# TM8_flash.net
KiCad netlist of a schematic drawn in EAGLE
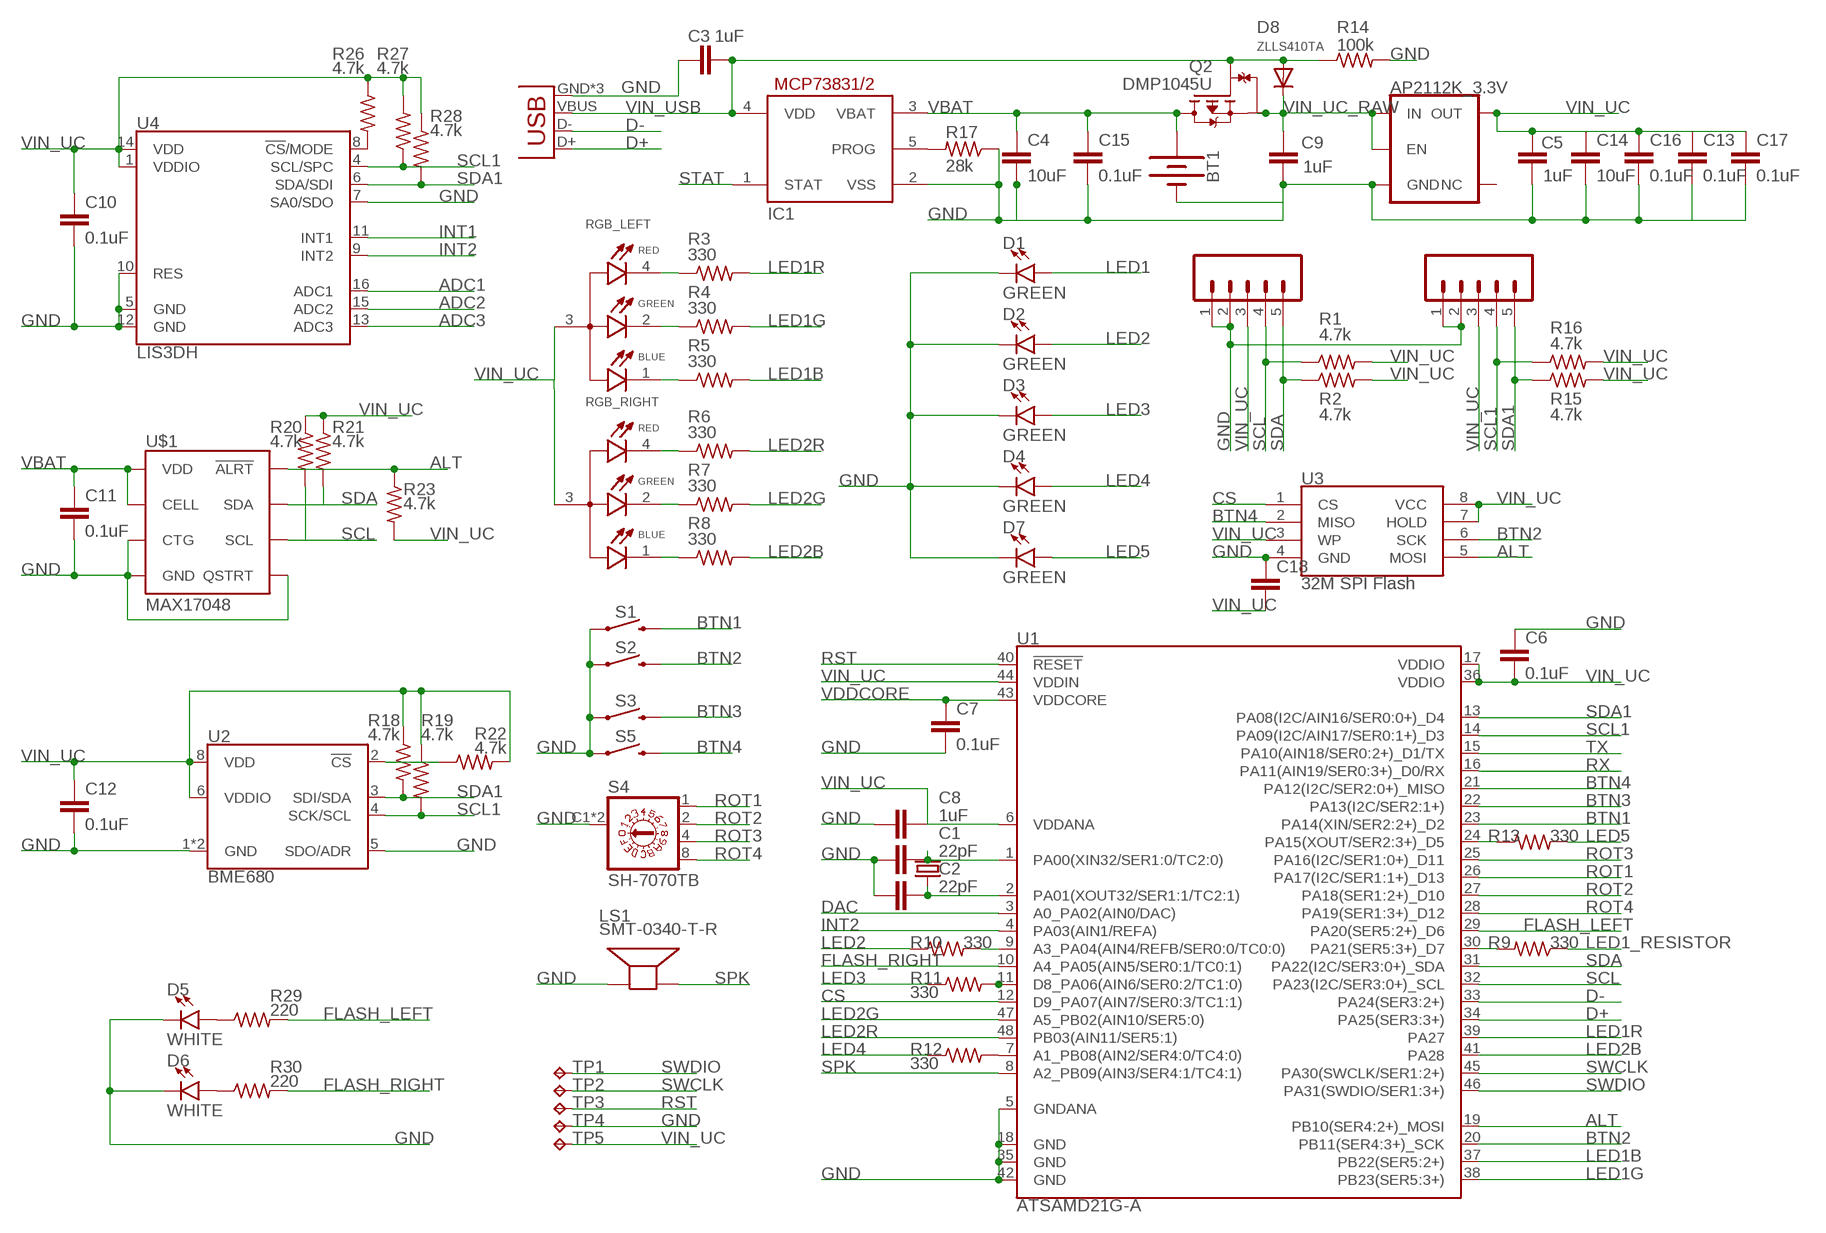
[diagram p0: schematic, sheet 1]

(export (version "E")
  (design (tool "Eeschema 10.0.6"))
  (components
    (comp (ref "AP2112K_3.3V")
      (value "3.3V")
      (footprint "eagle-import:SOT23-5")
      (libsource (lib "eagle-import") (part "V_REG_AP2112K-3.3V"))
    )
    (comp (ref "BT1")
      (value "BATTERY-20MM_SMD_4LEGS_OVERPASTE_INNER")
      (footprint "eagle-import:BATTCON_20MM_4LEGS_OVERPASTE_INNER")
      (libsource (lib "eagle-import") (part "BATTERY-20MM_SMD_4LEGS_OVERPASTE_INNER"))
    )
    (comp (ref "C1")
      (value "22pF")
      (footprint "eagle-import:C0402")
      (libsource (lib "eagle-import") (part "C-EUC0402"))
    )
    (comp (ref "C2")
      (value "22pF")
      (footprint "eagle-import:C0402")
      (libsource (lib "eagle-import") (part "C-EUC0402"))
    )
    (comp (ref "C3")
      (value "1uF")
      (footprint "eagle-import:C0402")
      (libsource (lib "eagle-import") (part "C-EUC0402"))
    )
    (comp (ref "C4")
      (value "10uF")
      (footprint "eagle-import:C0402")
      (libsource (lib "eagle-import") (part "C-EUC0402"))
    )
    (comp (ref "C5")
      (value "1uF")
      (footprint "eagle-import:C0402")
      (libsource (lib "eagle-import") (part "C-EUC0402"))
    )
    (comp (ref "C6")
      (value "0.1uF")
      (footprint "eagle-import:C0402")
      (libsource (lib "eagle-import") (part "C-EUC0402"))
    )
    (comp (ref "C7")
      (value "0.1uF")
      (footprint "eagle-import:C0402")
      (libsource (lib "eagle-import") (part "C-EUC0402"))
    )
    (comp (ref "C8")
      (value "1uF")
      (footprint "eagle-import:C0402")
      (libsource (lib "eagle-import") (part "C-EUC0402"))
    )
    (comp (ref "C9")
      (value "1uF")
      (footprint "eagle-import:C0402")
      (libsource (lib "eagle-import") (part "C-EUC0402"))
    )
    (comp (ref "C10")
      (value "0.1uF")
      (footprint "eagle-import:C0402")
      (libsource (lib "eagle-import") (part "C-EUC0402"))
    )
    (comp (ref "C11")
      (value "0.1uF")
      (footprint "eagle-import:C0402")
      (libsource (lib "eagle-import") (part "C-EUC0402"))
    )
    (comp (ref "C12")
      (value "0.1uF")
      (footprint "eagle-import:C0402")
      (libsource (lib "eagle-import") (part "C-EUC0402"))
    )
    (comp (ref "C13")
      (value "0.1uF")
      (footprint "eagle-import:C0402")
      (libsource (lib "eagle-import") (part "C-EUC0402"))
    )
    (comp (ref "C14")
      (value "10uF")
      (footprint "eagle-import:C0402")
      (libsource (lib "eagle-import") (part "C-EUC0402"))
    )
    (comp (ref "C15")
      (value "0.1uF")
      (footprint "eagle-import:C0402")
      (libsource (lib "eagle-import") (part "C-EUC0402"))
    )
    (comp (ref "C16")
      (value "0.1uF")
      (footprint "eagle-import:C0402")
      (libsource (lib "eagle-import") (part "C-EUC0402"))
    )
    (comp (ref "C17")
      (value "0.1uF")
      (footprint "eagle-import:C0402")
      (libsource (lib "eagle-import") (part "C-EUC0402"))
    )
    (comp (ref "C18")
      (value "C-EUC0402")
      (footprint "eagle-import:C0402")
      (libsource (lib "eagle-import") (part "C-EUC0402"))
    )
    (comp (ref "D1")
      (value "GREEN")
      (footprint "eagle-import:LED-1206")
      (libsource (lib "eagle-import") (part "LED-GREEN1206"))
    )
    (comp (ref "D2")
      (value "GREEN")
      (footprint "eagle-import:LED-1206")
      (libsource (lib "eagle-import") (part "LED-GREEN1206"))
    )
    (comp (ref "D3")
      (value "GREEN")
      (footprint "eagle-import:LED-1206")
      (libsource (lib "eagle-import") (part "LED-GREEN1206"))
    )
    (comp (ref "D4")
      (value "GREEN")
      (footprint "eagle-import:LED-1206")
      (libsource (lib "eagle-import") (part "LED-GREEN1206"))
    )
    (comp (ref "D5")
      (value "WHITE")
      (footprint "eagle-import:LED-1206")
      (libsource (lib "eagle-import") (part "LED-WHITE1206"))
    )
    (comp (ref "D6")
      (value "WHITE")
      (footprint "eagle-import:LED-1206")
      (libsource (lib "eagle-import") (part "LED-WHITE1206"))
    )
    (comp (ref "D7")
      (value "GREEN")
      (footprint "eagle-import:LED-1206")
      (libsource (lib "eagle-import") (part "LED-GREEN1206"))
    )
    (comp (ref "D8")
      (value "ZLLS410TA")
      (footprint "eagle-import:SOD-323F")
      (libsource (lib "eagle-import") (part "DIODESOD-323F"))
    )
    (comp (ref "IC1")
      (value "MCP73831/OT")
      (footprint "eagle-import:SOT23-5L")
      (libsource (lib "eagle-import") (part "MCP73831/OT"))
    )
    (comp (ref "JP2")
      (value "USB-MICROB")
      (footprint "eagle-import:USB-MICROB")
      (libsource (lib "eagle-import") (part "USB-MICROB"))
    )
    (comp (ref "LCD1")
      (value "CONN_05VERT_FEMALE_HEADER")
      (footprint "eagle-import:1X05_SMD_VERTICAL_COMBO")
      (libsource (lib "eagle-import") (part "CONN_05VERT_FEMALE_HEADER"))
    )
    (comp (ref "LCD2")
      (value "CONN_05VERT_FEMALE_HEADER")
      (footprint "eagle-import:1X05_SMD_VERTICAL_COMBO")
      (libsource (lib "eagle-import") (part "CONN_05VERT_FEMALE_HEADER"))
    )
    (comp (ref "LS1")
      (value "SMT-0340-T-R")
      (footprint "eagle-import:XDCR_SMT-0340-T-R")
      (fields (field (name "MANUFACTURER") "Pui Audio"))
      (libsource (lib "eagle-import") (part "SMT-0340-T-R"))
    )
    (comp (ref "Q2")
      (value "DMP1045U")
      (footprint "eagle-import:SOT91P240X110-3N")
      (fields (field (name "MF") "Diodes Inc."))
      (libsource (lib "eagle-import") (part "DMP1045U"))
    )
    (comp (ref "R1")
      (value "4.7k")
      (footprint "eagle-import:R0402")
      (libsource (lib "eagle-import") (part "rcl_334_R-US_R0402"))
    )
    (comp (ref "R2")
      (value "4.7k")
      (footprint "eagle-import:R0402")
      (libsource (lib "eagle-import") (part "rcl_334_R-US_R0402"))
    )
    (comp (ref "R3")
      (value "330")
      (footprint "eagle-import:R0402")
      (libsource (lib "eagle-import") (part "rcl_334_R-US_R0402"))
    )
    (comp (ref "R4")
      (value "330")
      (footprint "eagle-import:R0402")
      (libsource (lib "eagle-import") (part "rcl_334_R-US_R0402"))
    )
    (comp (ref "R5")
      (value "330")
      (footprint "eagle-import:R0402")
      (libsource (lib "eagle-import") (part "rcl_334_R-US_R0402"))
    )
    (comp (ref "R6")
      (value "330")
      (footprint "eagle-import:R0402")
      (libsource (lib "eagle-import") (part "rcl_334_R-US_R0402"))
    )
    (comp (ref "R7")
      (value "330")
      (footprint "eagle-import:R0402")
      (libsource (lib "eagle-import") (part "rcl_334_R-US_R0402"))
    )
    (comp (ref "R8")
      (value "330")
      (footprint "eagle-import:R0402")
      (libsource (lib "eagle-import") (part "rcl_334_R-US_R0402"))
    )
    (comp (ref "R9")
      (value "330")
      (footprint "eagle-import:R0402")
      (libsource (lib "eagle-import") (part "rcl_334_R-US_R0402"))
    )
    (comp (ref "R10")
      (value "330")
      (footprint "eagle-import:R0402")
      (libsource (lib "eagle-import") (part "rcl_334_R-US_R0402"))
    )
    (comp (ref "R11")
      (value "330")
      (footprint "eagle-import:R0402")
      (libsource (lib "eagle-import") (part "rcl_334_R-US_R0402"))
    )
    (comp (ref "R12")
      (value "330")
      (footprint "eagle-import:R0402")
      (libsource (lib "eagle-import") (part "rcl_334_R-US_R0402"))
    )
    (comp (ref "R13")
      (value "330")
      (footprint "eagle-import:R0402")
      (libsource (lib "eagle-import") (part "rcl_334_R-US_R0402"))
    )
    (comp (ref "R14")
      (value "100k")
      (footprint "eagle-import:R0402")
      (libsource (lib "eagle-import") (part "R-US_R0402"))
    )
    (comp (ref "R15")
      (value "4.7k")
      (footprint "eagle-import:R0402")
      (libsource (lib "eagle-import") (part "rcl_334_R-US_R0402"))
    )
    (comp (ref "R16")
      (value "4.7k")
      (footprint "eagle-import:R0402")
      (libsource (lib "eagle-import") (part "rcl_334_R-US_R0402"))
    )
    (comp (ref "R17")
      (value "28k")
      (footprint "eagle-import:R0402")
      (libsource (lib "eagle-import") (part "adafruit_25768682_R-US_R0402"))
    )
    (comp (ref "R18")
      (value "4.7k")
      (footprint "eagle-import:R0402")
      (libsource (lib "eagle-import") (part "rcl_334_R-US_R0402"))
    )
    (comp (ref "R19")
      (value "4.7k")
      (footprint "eagle-import:R0402")
      (libsource (lib "eagle-import") (part "rcl_334_R-US_R0402"))
    )
    (comp (ref "R20")
      (value "4.7k")
      (footprint "eagle-import:R0402")
      (libsource (lib "eagle-import") (part "rcl_334_R-US_R0402"))
    )
    (comp (ref "R21")
      (value "4.7k")
      (footprint "eagle-import:R0402")
      (libsource (lib "eagle-import") (part "rcl_334_R-US_R0402"))
    )
    (comp (ref "R22")
      (value "4.7k")
      (footprint "eagle-import:R0402")
      (libsource (lib "eagle-import") (part "rcl_334_R-US_R0402"))
    )
    (comp (ref "R23")
      (value "4.7k")
      (footprint "eagle-import:R0402")
      (libsource (lib "eagle-import") (part "rcl_334_R-US_R0402"))
    )
    (comp (ref "R26")
      (value "4.7k")
      (footprint "eagle-import:R0402")
      (libsource (lib "eagle-import") (part "rcl_334_R-US_R0402"))
    )
    (comp (ref "R27")
      (value "4.7k")
      (footprint "eagle-import:R0402")
      (libsource (lib "eagle-import") (part "rcl_334_R-US_R0402"))
    )
    (comp (ref "R28")
      (value "4.7k")
      (footprint "eagle-import:R0402")
      (libsource (lib "eagle-import") (part "rcl_334_R-US_R0402"))
    )
    (comp (ref "R29")
      (value "220")
      (footprint "eagle-import:R0402")
      (libsource (lib "eagle-import") (part "rcl_334_R-US_R0402"))
    )
    (comp (ref "R30")
      (value "220")
      (footprint "eagle-import:R0402")
      (libsource (lib "eagle-import") (part "rcl_334_R-US_R0402"))
    )
    (comp (ref "RGB_LEFT")
      (value "EAST1616RGBA3")
      (footprint "eagle-import:LED_EAST1616RGBA3")
      (fields (field (name "MF") "Everlight Electronics"))
      (libsource (lib "eagle-import") (part "EAST1616RGBA3"))
    )
    (comp (ref "RGB_RIGHT")
      (value "EAST1616RGBA3")
      (footprint "eagle-import:LED_EAST1616RGBA3")
      (fields (field (name "MF") "Everlight Electronics"))
      (libsource (lib "eagle-import") (part "EAST1616RGBA3"))
    )
    (comp (ref "S1")
      (value "MOMENTARY-SWITCH-SPST-SMD-6.0X3.5MM")
      (footprint "eagle-import:TACTILE_SWITCH_SMD_6.0X3.5MM")
      (libsource (lib "eagle-import") (part "MOMENTARY-SWITCH-SPST-SMD-6.0X3.5MM"))
    )
    (comp (ref "S2")
      (value "MOMENTARY-SWITCH-SPST-SMD-6.0X3.5MM")
      (footprint "eagle-import:TACTILE_SWITCH_SMD_6.0X3.5MM")
      (libsource (lib "eagle-import") (part "MOMENTARY-SWITCH-SPST-SMD-6.0X3.5MM"))
    )
    (comp (ref "S3")
      (value "MOMENTARY-SWITCH-SPST-SMD-6.0X3.5MM")
      (footprint "eagle-import:TACTILE_SWITCH_SMD_6.0X3.5MM")
      (libsource (lib "eagle-import") (part "MOMENTARY-SWITCH-SPST-SMD-6.0X3.5MM"))
    )
    (comp (ref "S4")
      (value "SH-7070TB")
      (footprint "eagle-import:SH-7070B")
      (fields (field (name "MF") "Nidec Copal"))
      (libsource (lib "eagle-import") (part "SH-7070TB"))
    )
    (comp (ref "S5")
      (value "MOMENTARY-SWITCH-SPST-SMD-6.0X3.5MM")
      (footprint "eagle-import:TACTILE_SWITCH_SMD_6.0X3.5MM")
      (libsource (lib "eagle-import") (part "MOMENTARY-SWITCH-SPST-SMD-6.0X3.5MM"))
    )
    (comp (ref "TP1")
      (value "TPTP14R")
      (footprint "eagle-import:TP14R")
      (libsource (lib "eagle-import") (part "TPTP14R"))
    )
    (comp (ref "TP2")
      (value "TPTP14R")
      (footprint "eagle-import:TP14R")
      (libsource (lib "eagle-import") (part "TPTP14R"))
    )
    (comp (ref "TP3")
      (value "TPTP11R")
      (footprint "eagle-import:TP11R")
      (libsource (lib "eagle-import") (part "TPTP11R"))
    )
    (comp (ref "TP4")
      (value "TPTP14R")
      (footprint "eagle-import:TP14R")
      (libsource (lib "eagle-import") (part "TPTP14R"))
    )
    (comp (ref "TP5")
      (value "TPTP14R")
      (footprint "eagle-import:TP14R")
      (libsource (lib "eagle-import") (part "TPTP14R"))
    )
    (comp (ref "U$1")
      (value "MAX17048")
      (footprint "eagle-import:DFN-8")
      (libsource (lib "eagle-import") (part "MAX17048DFN8"))
    )
    (comp (ref "U1")
      (value "ATSAMD21G-A")
      (footprint "eagle-import:TQFP-48")
      (libsource (lib "eagle-import") (part "ATSAMD21G-A"))
    )
    (comp (ref "U2")
      (value "BME680")
      (footprint "eagle-import:LGA3.0X3.0")
      (libsource (lib "eagle-import") (part "BME680-LGA"))
    )
    (comp (ref "U3")
      (value "32M SPI Flash")
      (footprint "eagle-import:SO08")
      (libsource (lib "eagle-import") (part "SPI_FLASH-X25XXSMD"))
    )
    (comp (ref "U4")
      (value "LIS3DH")
      (footprint "eagle-import:LGA-16-3X3")
      (libsource (lib "eagle-import") (part "LIS3DH"))
    )
    (comp (ref "Y1")
      (value "32.768kHz")
      (footprint "eagle-import:CRYSTAL-SMD-3.2X1.5MM")
      (libsource (lib "eagle-import") (part "CRYSTAL-32.768KHZSMD-3.2X1.5"))
    )
  )
  (nets
    (net (code "1") (name "/ADC1") (class "Default")
      (node (ref "U4") (pin "16") (pinfunction "ADC1_16") (pintype "bidirectional"))
    )
    (net (code "2") (name "/ADC2") (class "Default")
      (node (ref "U4") (pin "15") (pinfunction "ADC2_15") (pintype "bidirectional"))
    )
    (net (code "3") (name "/ADC3") (class "Default")
      (node (ref "U4") (pin "13") (pinfunction "ADC3_13") (pintype "bidirectional"))
    )
    (net (code "4") (name "/ALT") (class "Default")
      (node (ref "R23") (pin "1") (pinfunction "1_1") (pintype "passive"))
      (node (ref "U$1") (pin "P$5") (pinfunction "~{ALRT}_P$5") (pintype "bidirectional"))
      (node (ref "U1") (pin "19") (pinfunction "PB10(SER4:2+)_MOSI_19") (pintype "bidirectional"))
      (node (ref "U3") (pin "5") (pinfunction "MOSI_5") (pintype "bidirectional"))
    )
    (net (code "5") (name "/BTN1") (class "Default")
      (node (ref "S1") (pin "2") (pinfunction "2_2") (pintype "passive"))
      (node (ref "U1") (pin "23") (pinfunction "PA14(XIN/SER2:2+)_D2_23") (pintype "bidirectional"))
    )
    (net (code "6") (name "/BTN2") (class "Default")
      (node (ref "S2") (pin "2") (pinfunction "2_2") (pintype "passive"))
      (node (ref "U1") (pin "20") (pinfunction "PB11(SER4:3+)_SCK_20") (pintype "bidirectional"))
      (node (ref "U3") (pin "6") (pinfunction "SCK_6") (pintype "bidirectional"))
    )
    (net (code "7") (name "/BTN3") (class "Default")
      (node (ref "S3") (pin "2") (pinfunction "2_2") (pintype "passive"))
      (node (ref "U1") (pin "22") (pinfunction "PA13(I2C/SER2:1+)_22") (pintype "bidirectional"))
    )
    (net (code "8") (name "/BTN4") (class "Default")
      (node (ref "S5") (pin "2") (pinfunction "2_2") (pintype "passive"))
      (node (ref "U1") (pin "21") (pinfunction "PA12(I2C/SER2:0+)_MISO_21") (pintype "bidirectional"))
      (node (ref "U3") (pin "2") (pinfunction "MISO_2") (pintype "bidirectional"))
    )
    (net (code "9") (name "/CS") (class "Default")
      (node (ref "U1") (pin "12") (pinfunction "D9_PA07(AIN7/SER0:3/TC1:1)_12") (pintype "bidirectional"))
      (node (ref "U3") (pin "1") (pinfunction "CS_1") (pintype "bidirectional"))
    )
    (net (code "10") (name "/D+") (class "Default")
      (node (ref "JP2") (pin "D+") (pinfunction "D+_D+") (pintype "bidirectional"))
      (node (ref "U1") (pin "34") (pinfunction "PA25(SER3:3+)_34") (pintype "bidirectional"))
    )
    (net (code "11") (name "/D-") (class "Default")
      (node (ref "JP2") (pin "D-") (pinfunction "D-_D-") (pintype "bidirectional"))
      (node (ref "U1") (pin "33") (pinfunction "PA24(SER3:2+)_33") (pintype "bidirectional"))
    )
    (net (code "12") (name "/DAC") (class "Default")
      (node (ref "U1") (pin "3") (pinfunction "A0_PA02(AIN0/DAC)_3") (pintype "bidirectional"))
    )
    (net (code "13") (name "/FLASH_LEFT") (class "Default")
      (node (ref "R29") (pin "2") (pinfunction "2_2") (pintype "passive"))
      (node (ref "U1") (pin "29") (pinfunction "PA20(SER5:2+)_D6_29") (pintype "bidirectional"))
    )
    (net (code "14") (name "/FLASH_RIGHT") (class "Default")
      (node (ref "R30") (pin "2") (pinfunction "2_2") (pintype "passive"))
      (node (ref "U1") (pin "10") (pinfunction "A4_PA05(AIN5/SER0:1/TC0:1)_10") (pintype "bidirectional"))
    )
    (net (code "15") (name "/GND") (class "Default")
      (node (ref "AP2112K_3.3V") (pin "2") (pinfunction "GND_2") (pintype "input"))
      (node (ref "BT1") (pin "2") (pinfunction "-_2") (pintype "power_in"))
      (node (ref "C1") (pin "1") (pinfunction "1_1") (pintype "passive"))
      (node (ref "C10") (pin "2") (pinfunction "2_2") (pintype "passive"))
      (node (ref "C11") (pin "2") (pinfunction "2_2") (pintype "passive"))
      (node (ref "C12") (pin "2") (pinfunction "2_2") (pintype "passive"))
      (node (ref "C13") (pin "2") (pinfunction "2_2") (pintype "passive"))
      (node (ref "C14") (pin "2") (pinfunction "2_2") (pintype "passive"))
      (node (ref "C15") (pin "2") (pinfunction "2_2") (pintype "passive"))
      (node (ref "C16") (pin "2") (pinfunction "2_2") (pintype "passive"))
      (node (ref "C17") (pin "2") (pinfunction "2_2") (pintype "passive"))
      (node (ref "C18") (pin "1") (pinfunction "1_1") (pintype "passive"))
      (node (ref "C2") (pin "1") (pinfunction "1_1") (pintype "passive"))
      (node (ref "C3") (pin "1") (pinfunction "1_1") (pintype "passive"))
      (node (ref "C4") (pin "2") (pinfunction "2_2") (pintype "passive"))
      (node (ref "C5") (pin "2") (pinfunction "2_2") (pintype "passive"))
      (node (ref "C6") (pin "1") (pinfunction "1_1") (pintype "passive"))
      (node (ref "C7") (pin "2") (pinfunction "2_2") (pintype "passive"))
      (node (ref "C8") (pin "1") (pinfunction "1_1") (pintype "passive"))
      (node (ref "C9") (pin "2") (pinfunction "2_2") (pintype "passive"))
      (node (ref "D1") (pin "C") (pinfunction "C_C") (pintype "passive"))
      (node (ref "D2") (pin "C") (pinfunction "C_C") (pintype "passive"))
      (node (ref "D3") (pin "C") (pinfunction "C_C") (pintype "passive"))
      (node (ref "D4") (pin "C") (pinfunction "C_C") (pintype "passive"))
      (node (ref "D5") (pin "C") (pinfunction "C_C") (pintype "passive"))
      (node (ref "D6") (pin "C") (pinfunction "C_C") (pintype "passive"))
      (node (ref "D7") (pin "C") (pinfunction "C_C") (pintype "passive"))
      (node (ref "IC1") (pin "2") (pinfunction "VSS_2") (pintype "power_in"))
      (node (ref "JP2") (pin "GND") (pinfunction "GND_GND") (pintype "bidirectional"))
      (node (ref "JP2") (pin "MT1") (pinfunction "GND_MT1") (pintype "bidirectional"))
      (node (ref "JP2") (pin "MT2") (pinfunction "GND_MT2") (pintype "bidirectional"))
      (node (ref "LCD1") (pin "1") (pinfunction "1_1") (pintype "passive"))
      (node (ref "LCD1") (pin "2") (pinfunction "2_2") (pintype "passive"))
      (node (ref "LCD2") (pin "1") (pinfunction "1_1") (pintype "passive"))
      (node (ref "LCD2") (pin "2") (pinfunction "2_2") (pintype "passive"))
      (node (ref "LS1") (pin "P") (pinfunction "P_P") (pintype "passive"))
      (node (ref "R14") (pin "2") (pinfunction "2_2") (pintype "passive"))
      (node (ref "R17") (pin "1") (pinfunction "1_1") (pintype "passive"))
      (node (ref "S1") (pin "1") (pinfunction "1_1") (pintype "passive"))
      (node (ref "S2") (pin "1") (pinfunction "1_1") (pintype "passive"))
      (node (ref "S3") (pin "1") (pinfunction "1_1") (pintype "passive"))
      (node (ref "S4") (pin "C1") (pinfunction "C_C1") (pintype "passive"))
      (node (ref "S4") (pin "C2") (pinfunction "C_C2") (pintype "passive"))
      (node (ref "S5") (pin "1") (pinfunction "1_1") (pintype "passive"))
      (node (ref "TP4") (pin "TP") (pinfunction "TP_TP") (pintype "input"))
      (node (ref "U$1") (pin "P$1") (pinfunction "CTG_P$1") (pintype "input"))
      (node (ref "U$1") (pin "P$4") (pinfunction "GND_P$4") (pintype "bidirectional"))
      (node (ref "U$1") (pin "P$6") (pinfunction "QSTRT_P$6") (pintype "bidirectional"))
      (node (ref "U$1") (pin "P$9") (pinfunction "GND_P$9") (pintype "bidirectional"))
      (node (ref "U1") (pin "18") (pinfunction "GND_18") (pintype "bidirectional"))
      (node (ref "U1") (pin "35") (pinfunction "GND_35") (pintype "bidirectional"))
      (node (ref "U1") (pin "42") (pinfunction "GND_42") (pintype "bidirectional"))
      (node (ref "U1") (pin "5") (pinfunction "GNDANA_5") (pintype "bidirectional"))
      (node (ref "U2") (pin "1") (pinfunction "GND_1") (pintype "bidirectional"))
      (node (ref "U2") (pin "5") (pinfunction "SDO/ADR_5") (pintype "bidirectional"))
      (node (ref "U2") (pin "7") (pinfunction "GND_7") (pintype "bidirectional"))
      (node (ref "U3") (pin "4") (pinfunction "GND_4") (pintype "power_in"))
      (node (ref "U4") (pin "10") (pinfunction "RES_10") (pintype "bidirectional"))
      (node (ref "U4") (pin "12") (pinfunction "GND_12") (pintype "bidirectional"))
      (node (ref "U4") (pin "5") (pinfunction "GND_5") (pintype "bidirectional"))
      (node (ref "U4") (pin "7") (pinfunction "SA0/SDO_7") (pintype "bidirectional"))
    )
    (net (code "16") (name "/INT1") (class "Default")
      (node (ref "U4") (pin "11") (pinfunction "INT1_11") (pintype "bidirectional"))
    )
    (net (code "17") (name "/INT2") (class "Default")
      (node (ref "U1") (pin "4") (pinfunction "PA03(AIN1/REFA)_4") (pintype "bidirectional"))
      (node (ref "U4") (pin "9") (pinfunction "INT2_9") (pintype "bidirectional"))
    )
    (net (code "18") (name "/LED1") (class "Default")
      (node (ref "D1") (pin "A") (pinfunction "A_A") (pintype "passive"))
    )
    (net (code "19") (name "/LED1B") (class "Default")
      (node (ref "R5") (pin "2") (pinfunction "2_2") (pintype "passive"))
      (node (ref "U1") (pin "37") (pinfunction "PB22(SER5:2+)_37") (pintype "bidirectional"))
    )
    (net (code "20") (name "/LED1G") (class "Default")
      (node (ref "R4") (pin "2") (pinfunction "2_2") (pintype "passive"))
      (node (ref "U1") (pin "38") (pinfunction "PB23(SER5:3+)_38") (pintype "bidirectional"))
    )
    (net (code "21") (name "/LED1R") (class "Default")
      (node (ref "R3") (pin "2") (pinfunction "2_2") (pintype "passive"))
      (node (ref "U1") (pin "39") (pinfunction "PA27_39") (pintype "bidirectional"))
    )
    (net (code "22") (name "/LED1_RESISTOR") (class "Default")
      (node (ref "R9") (pin "1") (pinfunction "1_1") (pintype "passive"))
    )
    (net (code "23") (name "/LED2") (class "Default")
      (node (ref "D2") (pin "A") (pinfunction "A_A") (pintype "passive"))
      (node (ref "R10") (pin "1") (pinfunction "1_1") (pintype "passive"))
    )
    (net (code "24") (name "/LED2B") (class "Default")
      (node (ref "R8") (pin "2") (pinfunction "2_2") (pintype "passive"))
      (node (ref "U1") (pin "41") (pinfunction "PA28_41") (pintype "bidirectional"))
    )
    (net (code "25") (name "/LED2G") (class "Default")
      (node (ref "R7") (pin "2") (pinfunction "2_2") (pintype "passive"))
      (node (ref "U1") (pin "47") (pinfunction "A5_PB02(AIN10/SER5:0)_47") (pintype "bidirectional"))
    )
    (net (code "26") (name "/LED2R") (class "Default")
      (node (ref "R6") (pin "2") (pinfunction "2_2") (pintype "passive"))
      (node (ref "U1") (pin "48") (pinfunction "PB03(AIN11/SER5:1)_48") (pintype "bidirectional"))
    )
    (net (code "27") (name "/LED3") (class "Default")
      (node (ref "D3") (pin "A") (pinfunction "A_A") (pintype "passive"))
      (node (ref "R11") (pin "1") (pinfunction "1_1") (pintype "passive"))
    )
    (net (code "28") (name "/LED4") (class "Default")
      (node (ref "D4") (pin "A") (pinfunction "A_A") (pintype "passive"))
      (node (ref "R12") (pin "1") (pinfunction "1_1") (pintype "passive"))
    )
    (net (code "29") (name "/LED5") (class "Default")
      (node (ref "D7") (pin "A") (pinfunction "A_A") (pintype "passive"))
      (node (ref "R13") (pin "2") (pinfunction "2_2") (pintype "passive"))
    )
    (net (code "30") (name "/ROT1") (class "Default")
      (node (ref "S4") (pin "1") (pinfunction "1_1") (pintype "passive"))
      (node (ref "U1") (pin "26") (pinfunction "PA17(I2C/SER1:1+)_D13_26") (pintype "bidirectional"))
    )
    (net (code "31") (name "/ROT2") (class "Default")
      (node (ref "S4") (pin "2") (pinfunction "2_2") (pintype "passive"))
      (node (ref "U1") (pin "27") (pinfunction "PA18(SER1:2+)_D10_27") (pintype "bidirectional"))
    )
    (net (code "32") (name "/ROT3") (class "Default")
      (node (ref "S4") (pin "4") (pinfunction "4_4") (pintype "passive"))
      (node (ref "U1") (pin "25") (pinfunction "PA16(I2C/SER1:0+)_D11_25") (pintype "bidirectional"))
    )
    (net (code "33") (name "/ROT4") (class "Default")
      (node (ref "S4") (pin "8") (pinfunction "8_8") (pintype "passive"))
      (node (ref "U1") (pin "28") (pinfunction "PA19(SER1:3+)_D12_28") (pintype "bidirectional"))
    )
    (net (code "34") (name "/RST") (class "Default")
      (node (ref "TP3") (pin "TP") (pinfunction "TP_TP") (pintype "input"))
      (node (ref "U1") (pin "40") (pinfunction "~{RESET}_40") (pintype "bidirectional"))
    )
    (net (code "35") (name "/RX") (class "Default")
      (node (ref "U1") (pin "16") (pinfunction "PA11(AIN19/SER0:3+)_D0/RX_16") (pintype "bidirectional"))
    )
    (net (code "36") (name "/SCL") (class "Default")
      (node (ref "LCD1") (pin "4") (pinfunction "4_4") (pintype "passive"))
      (node (ref "R1") (pin "1") (pinfunction "1_1") (pintype "passive"))
      (node (ref "R20") (pin "2") (pinfunction "2_2") (pintype "passive"))
      (node (ref "U$1") (pin "P$7") (pinfunction "SCL_P$7") (pintype "output"))
      (node (ref "U1") (pin "32") (pinfunction "PA23(I2C/SER3:0+)_SCL_32") (pintype "bidirectional"))
    )
    (net (code "37") (name "/SCL1") (class "Default")
      (node (ref "LCD2") (pin "4") (pinfunction "4_4") (pintype "passive"))
      (node (ref "R16") (pin "1") (pinfunction "1_1") (pintype "passive"))
      (node (ref "R19") (pin "2") (pinfunction "2_2") (pintype "passive"))
      (node (ref "R27") (pin "1") (pinfunction "1_1") (pintype "passive"))
      (node (ref "U1") (pin "14") (pinfunction "PA09(I2C/AIN17/SER0:1+)_D3_14") (pintype "bidirectional"))
      (node (ref "U2") (pin "4") (pinfunction "SCK/SCL_4") (pintype "bidirectional"))
      (node (ref "U4") (pin "4") (pinfunction "SCL/SPC_4") (pintype "bidirectional"))
    )
    (net (code "38") (name "/SDA") (class "Default")
      (node (ref "LCD1") (pin "5") (pinfunction "5_5") (pintype "passive"))
      (node (ref "R2") (pin "1") (pinfunction "1_1") (pintype "passive"))
      (node (ref "R21") (pin "2") (pinfunction "2_2") (pintype "passive"))
      (node (ref "U$1") (pin "P$8") (pinfunction "SDA_P$8") (pintype "input"))
      (node (ref "U1") (pin "31") (pinfunction "PA22(I2C/SER3:0+)_SDA_31") (pintype "bidirectional"))
    )
    (net (code "39") (name "/SDA1") (class "Default")
      (node (ref "LCD2") (pin "5") (pinfunction "5_5") (pintype "passive"))
      (node (ref "R15") (pin "1") (pinfunction "1_1") (pintype "passive"))
      (node (ref "R18") (pin "2") (pinfunction "2_2") (pintype "passive"))
      (node (ref "R28") (pin "2") (pinfunction "2_2") (pintype "passive"))
      (node (ref "U1") (pin "13") (pinfunction "PA08(I2C/AIN16/SER0:0+)_D4_13") (pintype "bidirectional"))
      (node (ref "U2") (pin "3") (pinfunction "SDI/SDA_3") (pintype "bidirectional"))
      (node (ref "U4") (pin "6") (pinfunction "SDA/SDI_6") (pintype "bidirectional"))
    )
    (net (code "40") (name "/SPK") (class "Default")
      (node (ref "LS1") (pin "N") (pinfunction "N_N") (pintype "passive"))
      (node (ref "U1") (pin "8") (pinfunction "A2_PB09(AIN3/SER4:1/TC4:1)_8") (pintype "bidirectional"))
    )
    (net (code "41") (name "/STAT") (class "Default")
      (node (ref "IC1") (pin "1") (pinfunction "STAT_1") (pintype "output"))
    )
    (net (code "42") (name "/SWCLK") (class "Default")
      (node (ref "TP2") (pin "TP") (pinfunction "TP_TP") (pintype "input"))
      (node (ref "U1") (pin "45") (pinfunction "PA30(SWCLK/SER1:2+)_45") (pintype "bidirectional"))
    )
    (net (code "43") (name "/SWDIO") (class "Default")
      (node (ref "TP1") (pin "TP") (pinfunction "TP_TP") (pintype "input"))
      (node (ref "U1") (pin "46") (pinfunction "PA31(SWDIO/SER1:3+)_46") (pintype "bidirectional"))
    )
    (net (code "44") (name "/TX") (class "Default")
      (node (ref "U1") (pin "15") (pinfunction "PA10(AIN18/SER0:2+)_D1/TX_15") (pintype "bidirectional"))
    )
    (net (code "45") (name "/VBAT") (class "Default")
      (node (ref "BT1") (pin "1") (pinfunction "+_1") (pintype "power_in"))
      (node (ref "C11") (pin "1") (pinfunction "1_1") (pintype "passive"))
      (node (ref "C15") (pin "1") (pinfunction "1_1") (pintype "passive"))
      (node (ref "C4") (pin "1") (pinfunction "1_1") (pintype "passive"))
      (node (ref "IC1") (pin "3") (pinfunction "VBAT_3") (pintype "bidirectional"))
      (node (ref "Q2") (pin "3") (pinfunction "D_3") (pintype "passive"))
      (node (ref "U$1") (pin "P$2") (pinfunction "CELL_P$2") (pintype "input"))
      (node (ref "U$1") (pin "P$3") (pinfunction "VDD_P$3") (pintype "bidirectional"))
    )
    (net (code "46") (name "/VDDCORE") (class "Default")
      (node (ref "C7") (pin "1") (pinfunction "1_1") (pintype "passive"))
      (node (ref "U1") (pin "43") (pinfunction "VDDCORE_43") (pintype "bidirectional"))
    )
    (net (code "47") (name "/VIN_UC") (class "Default")
      (node (ref "AP2112K_3.3V") (pin "5") (pinfunction "OUT_5") (pintype "passive"))
      (node (ref "C10") (pin "1") (pinfunction "1_1") (pintype "passive"))
      (node (ref "C12") (pin "1") (pinfunction "1_1") (pintype "passive"))
      (node (ref "C13") (pin "1") (pinfunction "1_1") (pintype "passive"))
      (node (ref "C14") (pin "1") (pinfunction "1_1") (pintype "passive"))
      (node (ref "C16") (pin "1") (pinfunction "1_1") (pintype "passive"))
      (node (ref "C17") (pin "1") (pinfunction "1_1") (pintype "passive"))
      (node (ref "C18") (pin "2") (pinfunction "2_2") (pintype "passive"))
      (node (ref "C5") (pin "1") (pinfunction "1_1") (pintype "passive"))
      (node (ref "C6") (pin "2") (pinfunction "2_2") (pintype "passive"))
      (node (ref "C8") (pin "2") (pinfunction "2_2") (pintype "passive"))
      (node (ref "LCD1") (pin "3") (pinfunction "3_3") (pintype "passive"))
      (node (ref "LCD2") (pin "3") (pinfunction "3_3") (pintype "passive"))
      (node (ref "R1") (pin "2") (pinfunction "2_2") (pintype "passive"))
      (node (ref "R15") (pin "2") (pinfunction "2_2") (pintype "passive"))
      (node (ref "R16") (pin "2") (pinfunction "2_2") (pintype "passive"))
      (node (ref "R18") (pin "1") (pinfunction "1_1") (pintype "passive"))
      (node (ref "R19") (pin "1") (pinfunction "1_1") (pintype "passive"))
      (node (ref "R2") (pin "2") (pinfunction "2_2") (pintype "passive"))
      (node (ref "R20") (pin "1") (pinfunction "1_1") (pintype "passive"))
      (node (ref "R21") (pin "1") (pinfunction "1_1") (pintype "passive"))
      (node (ref "R22") (pin "2") (pinfunction "2_2") (pintype "passive"))
      (node (ref "R23") (pin "2") (pinfunction "2_2") (pintype "passive"))
      (node (ref "R26") (pin "1") (pinfunction "1_1") (pintype "passive"))
      (node (ref "R27") (pin "2") (pinfunction "2_2") (pintype "passive"))
      (node (ref "R28") (pin "1") (pinfunction "1_1") (pintype "passive"))
      (node (ref "RGB_LEFT") (pin "3") (pinfunction "A_3") (pintype "passive"))
      (node (ref "RGB_RIGHT") (pin "3") (pinfunction "A_3") (pintype "passive"))
      (node (ref "TP5") (pin "TP") (pinfunction "TP_TP") (pintype "input"))
      (node (ref "U1") (pin "17") (pinfunction "VDDIO_17") (pintype "bidirectional"))
      (node (ref "U1") (pin "36") (pinfunction "VDDIO_36") (pintype "bidirectional"))
      (node (ref "U1") (pin "44") (pinfunction "VDDIN_44") (pintype "bidirectional"))
      (node (ref "U1") (pin "6") (pinfunction "VDDANA_6") (pintype "bidirectional"))
      (node (ref "U2") (pin "6") (pinfunction "VDDIO_6") (pintype "bidirectional"))
      (node (ref "U2") (pin "8") (pinfunction "VDD_8") (pintype "bidirectional"))
      (node (ref "U3") (pin "3") (pinfunction "WP_3") (pintype "bidirectional"))
      (node (ref "U3") (pin "7") (pinfunction "HOLD_7") (pintype "bidirectional"))
      (node (ref "U3") (pin "8") (pinfunction "VCC_8") (pintype "power_in"))
      (node (ref "U4") (pin "1") (pinfunction "VDDIO_1") (pintype "bidirectional"))
      (node (ref "U4") (pin "14") (pinfunction "VDD_14") (pintype "bidirectional"))
    )
    (net (code "48") (name "/VIN_UC_RAW") (class "Default")
      (node (ref "AP2112K_3.3V") (pin "1") (pinfunction "IN_1") (pintype "input"))
      (node (ref "AP2112K_3.3V") (pin "3") (pinfunction "EN_3") (pintype "input"))
      (node (ref "C9") (pin "1") (pinfunction "1_1") (pintype "passive"))
      (node (ref "D8") (pin "C") (pinfunction "C_C") (pintype "passive"))
      (node (ref "Q2") (pin "2") (pinfunction "S_2") (pintype "passive"))
    )
    (net (code "49") (name "/VIN_USB") (class "Default")
      (node (ref "C3") (pin "2") (pinfunction "2_2") (pintype "passive"))
      (node (ref "D8") (pin "A") (pinfunction "A_A") (pintype "passive"))
      (node (ref "IC1") (pin "4") (pinfunction "VDD_4") (pintype "power_in"))
      (node (ref "JP2") (pin "VBUS") (pinfunction "VBUS_VBUS") (pintype "bidirectional"))
      (node (ref "Q2") (pin "1") (pinfunction "G_1") (pintype "passive"))
      (node (ref "R14") (pin "1") (pinfunction "1_1") (pintype "passive"))
    )
    (net (code "50") (name "Net-(D5-PadA)") (class "Default")
      (node (ref "D5") (pin "A") (pinfunction "A_A") (pintype "passive"))
      (node (ref "R29") (pin "1") (pinfunction "1_1") (pintype "passive"))
    )
    (net (code "51") (name "Net-(D6-PadA)") (class "Default")
      (node (ref "D6") (pin "A") (pinfunction "A_A") (pintype "passive"))
      (node (ref "R30") (pin "1") (pinfunction "1_1") (pintype "passive"))
    )
    (net (code "52") (name "Net-(IC1-PROG)") (class "Default")
      (node (ref "IC1") (pin "5") (pinfunction "PROG_5") (pintype "input"))
      (node (ref "R17") (pin "2") (pinfunction "2_2") (pintype "passive"))
    )
    (net (code "53") (name "Net-(RGB_LEFT-B_C)") (class "Default")
      (node (ref "R5") (pin "1") (pinfunction "1_1") (pintype "passive"))
      (node (ref "RGB_LEFT") (pin "1") (pinfunction "B_C_1") (pintype "passive"))
    )
    (net (code "54") (name "Net-(RGB_LEFT-G_C)") (class "Default")
      (node (ref "R4") (pin "1") (pinfunction "1_1") (pintype "passive"))
      (node (ref "RGB_LEFT") (pin "2") (pinfunction "G_C_2") (pintype "passive"))
    )
    (net (code "55") (name "Net-(RGB_LEFT-R_C)") (class "Default")
      (node (ref "R3") (pin "1") (pinfunction "1_1") (pintype "passive"))
      (node (ref "RGB_LEFT") (pin "4") (pinfunction "R_C_4") (pintype "passive"))
    )
    (net (code "56") (name "Net-(RGB_RIGHT-B_C)") (class "Default")
      (node (ref "R8") (pin "1") (pinfunction "1_1") (pintype "passive"))
      (node (ref "RGB_RIGHT") (pin "1") (pinfunction "B_C_1") (pintype "passive"))
    )
    (net (code "57") (name "Net-(RGB_RIGHT-G_C)") (class "Default")
      (node (ref "R7") (pin "1") (pinfunction "1_1") (pintype "passive"))
      (node (ref "RGB_RIGHT") (pin "2") (pinfunction "G_C_2") (pintype "passive"))
    )
    (net (code "58") (name "Net-(RGB_RIGHT-R_C)") (class "Default")
      (node (ref "R6") (pin "1") (pinfunction "1_1") (pintype "passive"))
      (node (ref "RGB_RIGHT") (pin "4") (pinfunction "R_C_4") (pintype "passive"))
    )
    (net (code "59") (name "Net-(U1-A1_PB08(AIN2{slash}SER4:0{slash}TC4:0))") (class "Default")
      (node (ref "R12") (pin "2") (pinfunction "2_2") (pintype "passive"))
      (node (ref "U1") (pin "7") (pinfunction "A1_PB08(AIN2/SER4:0/TC4:0)_7") (pintype "bidirectional"))
    )
    (net (code "60") (name "Net-(U1-A3_PA04(AIN4{slash}REFB{slash}SER0:0{slash}TC0:0))") (class "Default")
      (node (ref "R10") (pin "2") (pinfunction "2_2") (pintype "passive"))
      (node (ref "U1") (pin "9") (pinfunction "A3_PA04(AIN4/REFB/SER0:0/TC0:0)_9") (pintype "bidirectional"))
    )
    (net (code "61") (name "Net-(U1-D8_PA06(AIN6{slash}SER0:2{slash}TC1:0))") (class "Default")
      (node (ref "R11") (pin "2") (pinfunction "2_2") (pintype "passive"))
      (node (ref "U1") (pin "11") (pinfunction "D8_PA06(AIN6/SER0:2/TC1:0)_11") (pintype "bidirectional"))
    )
    (net (code "62") (name "Net-(U1-PA00(XIN32{slash}SER1:0{slash}TC2:0))") (class "Default")
      (node (ref "C1") (pin "2") (pinfunction "2_2") (pintype "passive"))
      (node (ref "U1") (pin "1") (pinfunction "PA00(XIN32/SER1:0/TC2:0)_1") (pintype "bidirectional"))
      (node (ref "Y1") (pin "P$2") (pinfunction "2_P$2") (pintype "passive"))
    )
    (net (code "63") (name "Net-(U1-PA01(XOUT32{slash}SER1:1{slash}TC2:1))") (class "Default")
      (node (ref "C2") (pin "2") (pinfunction "2_2") (pintype "passive"))
      (node (ref "U1") (pin "2") (pinfunction "PA01(XOUT32/SER1:1/TC2:1)_2") (pintype "bidirectional"))
      (node (ref "Y1") (pin "P$1") (pinfunction "1_P$1") (pintype "passive"))
    )
    (net (code "64") (name "Net-(U1-PA15(XOUT{slash}SER2:3+)_D5)") (class "Default")
      (node (ref "R13") (pin "1") (pinfunction "1_1") (pintype "passive"))
      (node (ref "U1") (pin "24") (pinfunction "PA15(XOUT/SER2:3+)_D5_24") (pintype "bidirectional"))
    )
    (net (code "65") (name "Net-(U1-PA21(SER5:3+)_D7)") (class "Default")
      (node (ref "R9") (pin "2") (pinfunction "2_2") (pintype "passive"))
      (node (ref "U1") (pin "30") (pinfunction "PA21(SER5:3+)_D7_30") (pintype "bidirectional"))
    )
    (net (code "66") (name "Net-(U2-~{CS})") (class "Default")
      (node (ref "R22") (pin "1") (pinfunction "1_1") (pintype "passive"))
      (node (ref "U2") (pin "2") (pinfunction "~{CS}_2") (pintype "bidirectional"))
    )
    (net (code "67") (name "Net-(U4-~{CS}{slash}MODE)") (class "Default")
      (node (ref "R26") (pin "2") (pinfunction "2_2") (pintype "passive"))
      (node (ref "U4") (pin "8") (pinfunction "~{CS}/MODE_8") (pintype "bidirectional"))
    )
    (net (code "68") (name "unconnected-(AP2112K_3.3V-NC-Pad4)") (class "Default")
      (node (ref "AP2112K_3.3V") (pin "4") (pinfunction "NC_4") (pintype "no_connect"))
    )
  )
)
